# vis-spi-out.net
KiCad netlist of a schematic drawn in EAGLE
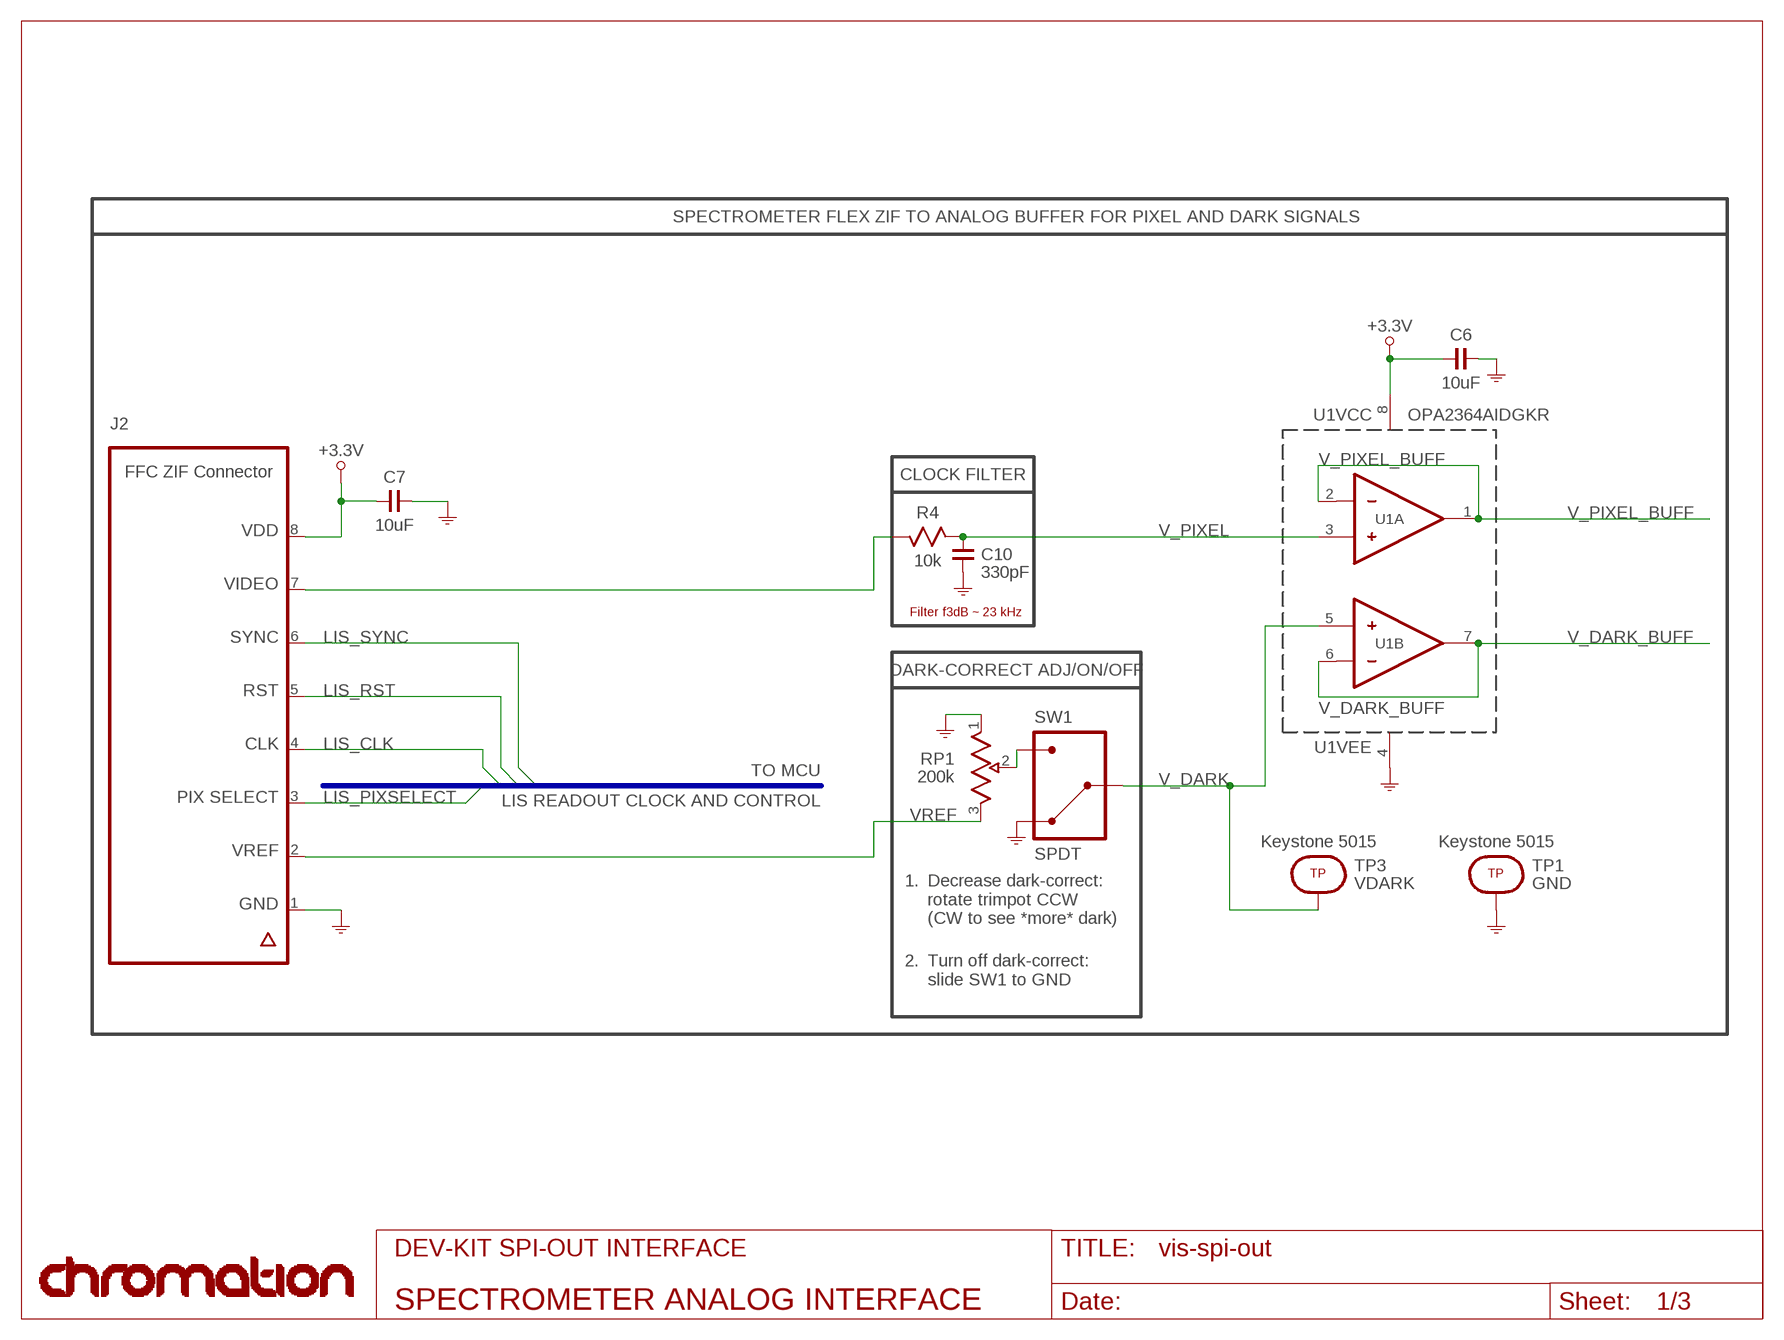
[diagram p0: schematic, sheet 1]
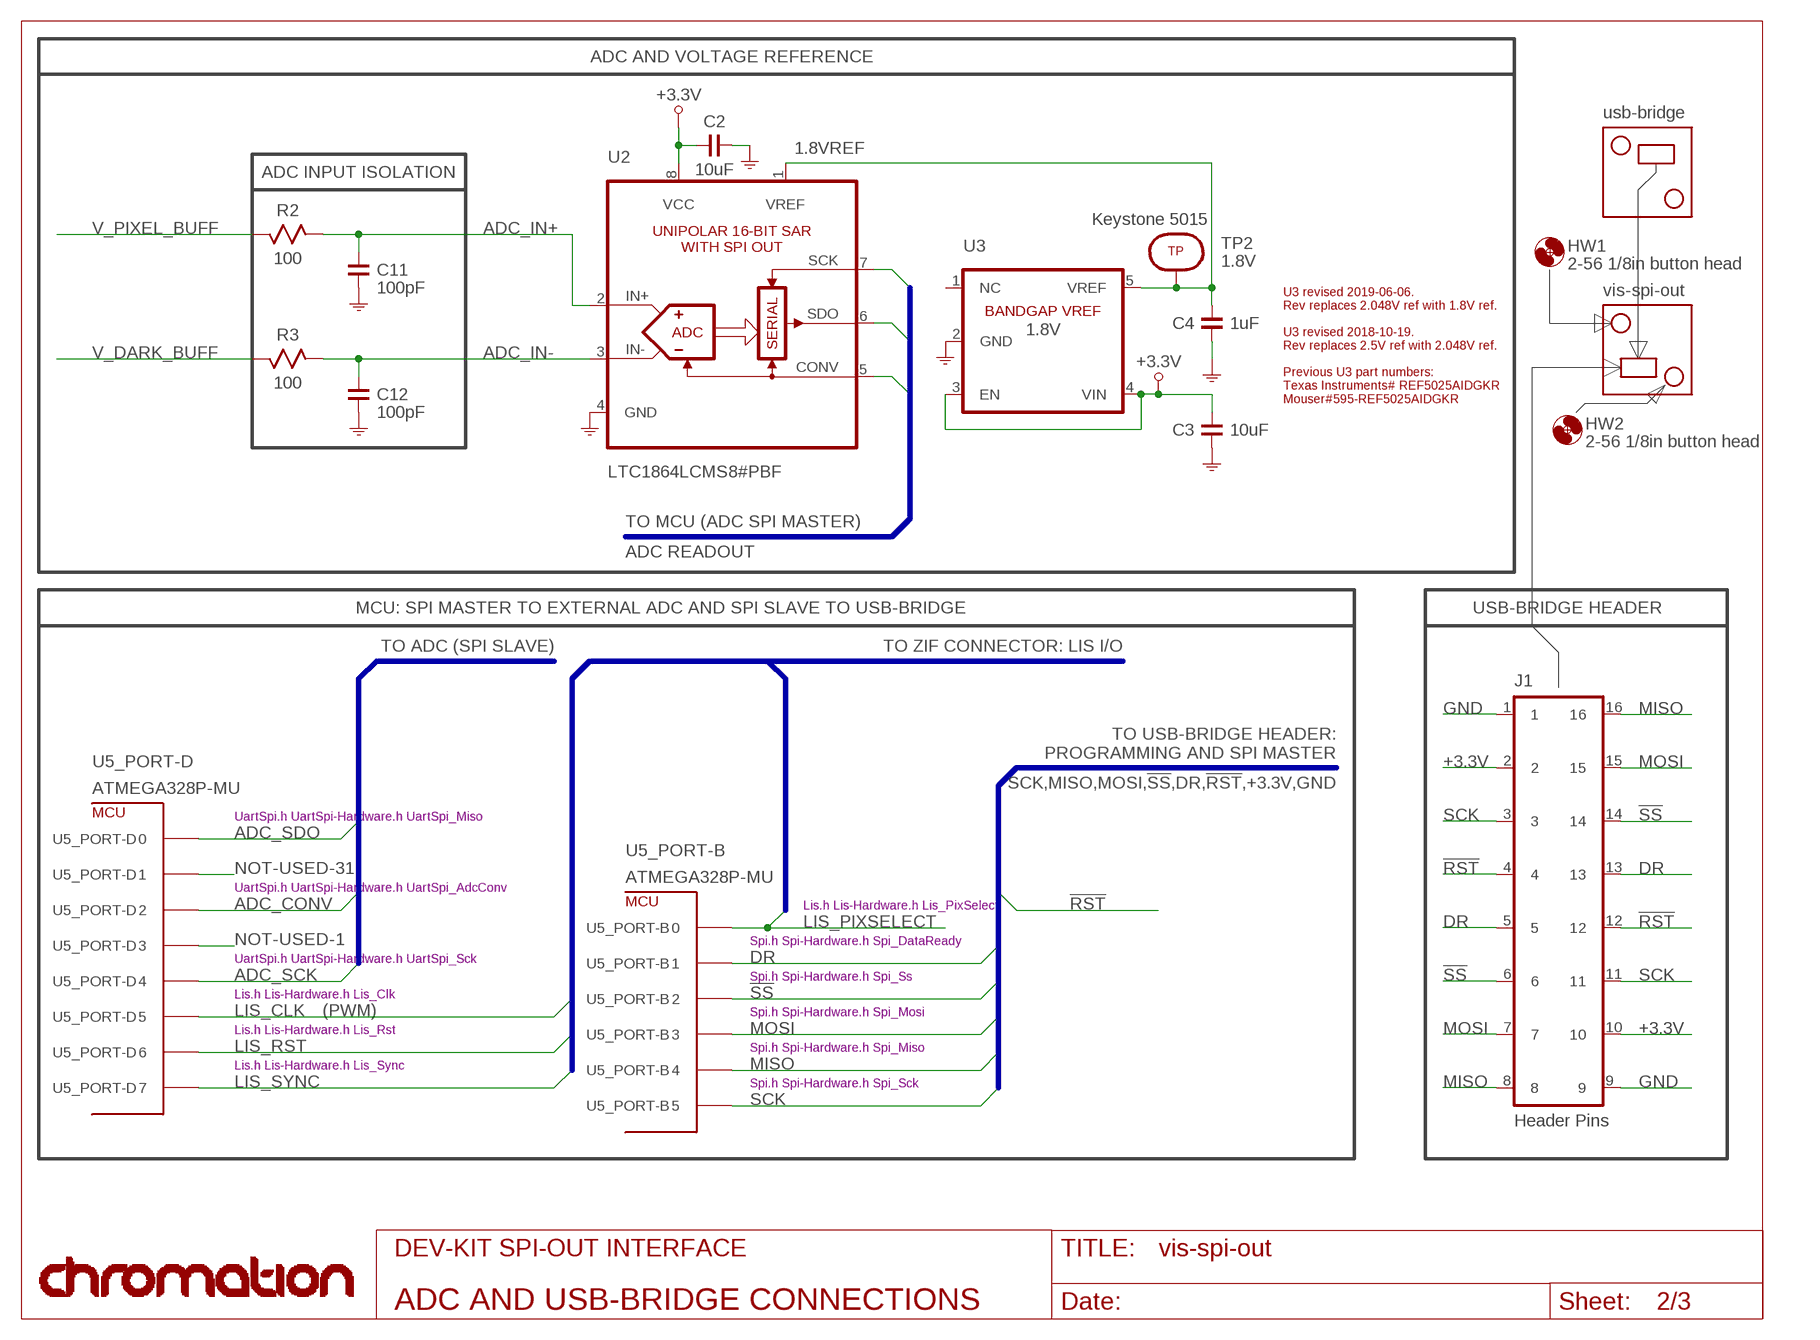
[diagram p1: schematic, sheet 2]
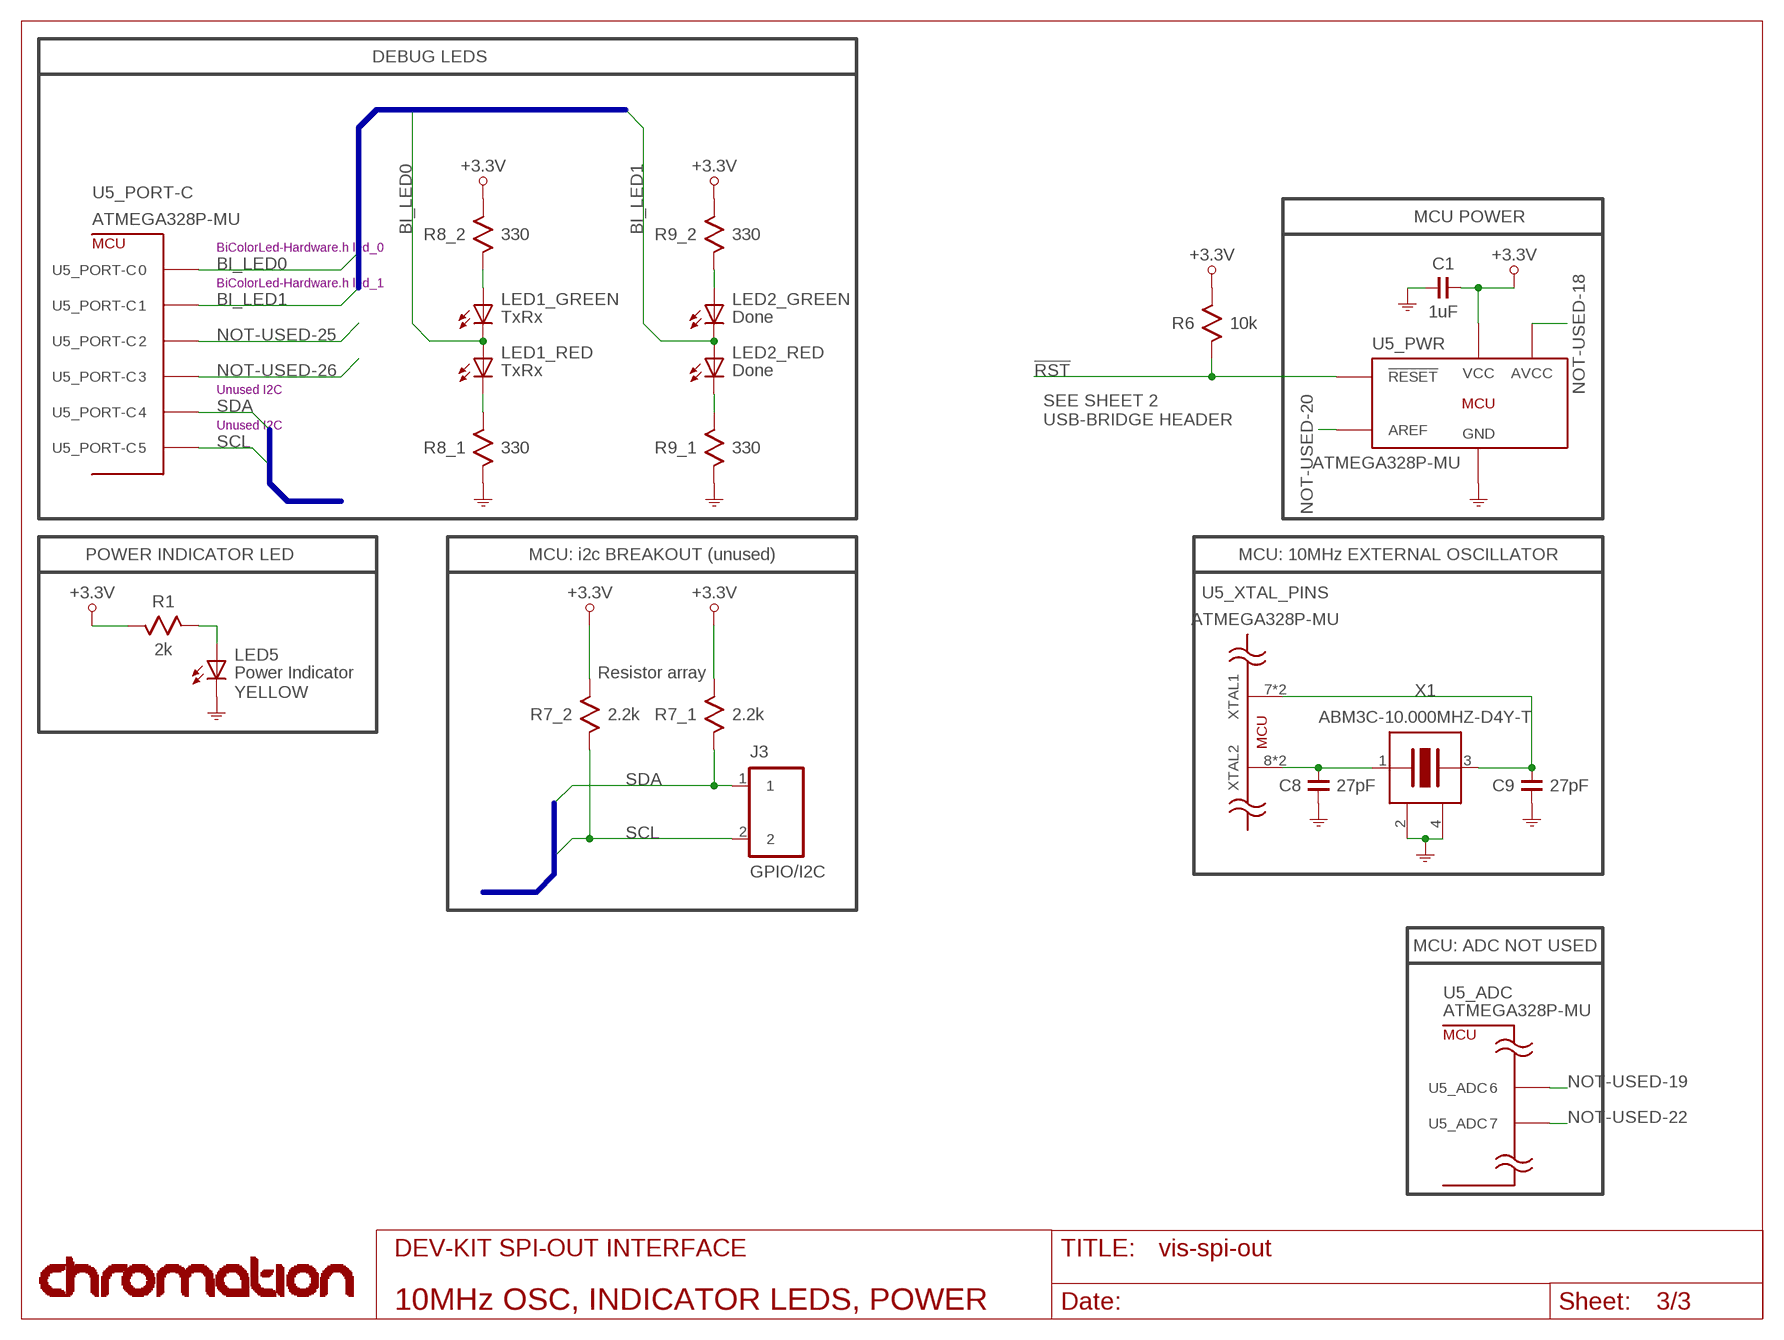
[diagram p2: schematic, sheet 3]

(export (version "E")
  (design (tool "Eeschema 10.0.6"))
  (components
    (comp (ref "C2")
      (value "10uF")
      (footprint "eagle-import:0603")
      (libsource (lib "eagle-import") (part "C_0603"))
    )
    (comp (ref "C3")
      (value "10uF")
      (footprint "eagle-import:0603")
      (libsource (lib "eagle-import") (part "C_0603"))
    )
    (comp (ref "C4")
      (value "1uF")
      (footprint "eagle-import:0603")
      (libsource (lib "eagle-import") (part "C_0603"))
    )
    (comp (ref "C11")
      (value "100pF")
      (footprint "eagle-import:0603")
      (libsource (lib "eagle-import") (part "C_0603"))
    )
    (comp (ref "C12")
      (value "100pF")
      (footprint "eagle-import:0603")
      (libsource (lib "eagle-import") (part "C_0603"))
    )
    (comp (ref "HW1")
      (value "2-56 1/8in button head")
      (footprint "eagle-import:MCMASTER_92949A081")
      (libsource (lib "eagle-import") (part "MOUNTING-HOLE_2-56_SCREW"))
    )
    (comp (ref "HW2")
      (value "2-56 1/8in button head")
      (footprint "eagle-import:MCMASTER_92949A081")
      (libsource (lib "eagle-import") (part "MOUNTING-HOLE_2-56_SCREW"))
    )
    (comp (ref "J1")
      (value "Header Pins")
      (footprint "eagle-import:TSM-108-01-S-DV")
      (libsource (lib "eagle-import") (part "HEADER-PIN_2X8"))
    )
    (comp (ref "R2")
      (value "100")
      (footprint "eagle-import:0603")
      (libsource (lib "eagle-import") (part "R_0603"))
    )
    (comp (ref "R3")
      (value "100")
      (footprint "eagle-import:0603")
      (libsource (lib "eagle-import") (part "R_0603"))
    )
    (comp (ref "ROTATED-USB-BRIDGE-PCB")
      (value "USB-BRIDGE_FOOTPRINT-AND-USB-REF")
      (footprint "eagle-import:OUTLINE-HEADER-MICROUSB")
      (libsource (lib "eagle-import") (part "USB-BRIDGE_FOOTPRINT-AND-USB-REF"))
    )
    (comp (ref "TP2")
      (value "Keystone 5015")
      (footprint "eagle-import:SMT-TEST-POINT-5015")
      (fields (field (name "TP_SIGNAL_NAME") "1.8V"))
      (libsource (lib "eagle-import") (part "TEST-POINT_SMT-5015"))
    )
    (comp (ref "U2")
      (value "LTC1864LCMS8#PBF")
      (footprint "eagle-import:LTC1864LCMS8")
      (libsource (lib "eagle-import") (part "LTC1864L_CMS8"))
    )
    (comp (ref "U3")
      (value "1.8V")
      (footprint "eagle-import:SOT23")
      (libsource (lib "eagle-import") (part "VREF_SOT23-LM4132"))
    )
    (comp (ref "U5")
      (value "ATMEGA328P-MU")
      (footprint "eagle-import:QFN-32_ATMEL")
      (fields
        (field (name "EXPORT") "YES")
        (field (name "MANUF") "Atmel")
        (field (name "MANUF_PNUM") "ATMEGA328P-MUR")
        (field (name "NOTES") "8-bit MCU: 10MHz at 3.3V, two SPI, and a PWM.")
        (field (name "VENDOR1") "Mouser")
        (field (name "VENDOR1_PNUM") "556-ATMEGA328P-MUR")
        (field (name "VENDOR1_PQ_00001") "3.57")
      )
      (libsource (lib "eagle-import") (part "ATMEGA328P-MU"))
    )
    (comp (ref "USB-BRDIGE-PCB")
      (value "USB-BRIDGE_FOOTPRINT-AND-USB-REF")
      (footprint "eagle-import:OUTLINE-HEADER-MICROUSB")
      (libsource (lib "eagle-import") (part "USB-BRIDGE_FOOTPRINT-AND-USB-REF"))
    )
    (comp (ref "C6")
      (value "10uF")
      (footprint "eagle-import:0603")
      (libsource (lib "eagle-import") (part "C_0603"))
    )
    (comp (ref "C7")
      (value "10uF")
      (footprint "eagle-import:0603")
      (libsource (lib "eagle-import") (part "C_0603"))
    )
    (comp (ref "C10")
      (value "330pF")
      (footprint "eagle-import:0603")
      (libsource (lib "eagle-import") (part "C_0603"))
    )
    (comp (ref "J2")
      (value "FFC ZIF Connector")
      (footprint "eagle-import:FH12-8S-0.5SH")
      (libsource (lib "eagle-import") (part "ZIF_8-PIN"))
    )
    (comp (ref "R4")
      (value "10k")
      (footprint "eagle-import:0603")
      (libsource (lib "eagle-import") (part "R_0603"))
    )
    (comp (ref "RP1")
      (value "200k")
      (footprint "eagle-import:TC3XX-2-204E")
      (libsource (lib "eagle-import") (part "TRIMPOT_3MM-SMD"))
    )
    (comp (ref "SW1")
      (value "SPDT")
      (footprint "eagle-import:JS102011JCQN")
      (libsource (lib "eagle-import") (part "SW_SPDT_JS102011JCQN"))
    )
    (comp (ref "TP1")
      (value "Keystone 5015")
      (footprint "eagle-import:SMT-TEST-POINT-5015")
      (fields (field (name "TP_SIGNAL_NAME") "GND"))
      (libsource (lib "eagle-import") (part "TEST-POINT_SMT-5015"))
    )
    (comp (ref "TP3")
      (value "Keystone 5015")
      (footprint "eagle-import:SMT-TEST-POINT-5015")
      (fields (field (name "TP_SIGNAL_NAME") "VDARK"))
      (libsource (lib "eagle-import") (part "TEST-POINT_SMT-5015"))
    )
    (comp (ref "U1")
      (value "OPA2364AIDGKR")
      (footprint "eagle-import:DGK")
      (fields
        (field (name "EXPORT") "YES")
        (field (name "MANUF") "Texas Instruments")
        (field (name "MANUF_PNUM") "OPA2364AIDGKR")
        (field (name "NOTES") "Dual op-amp to drive the SAR ADC S/H input. Settles to 0.01% (6.5LSB) in 1.5us.")
        (field (name "VENDOR1") "Mouser")
        (field (name "VENDOR1_PNUM") "595-OPA2364AIDGKR")
        (field (name "VENDOR1_PQ_00001") "2.64")
      )
      (libsource (lib "eagle-import") (part "OPA2364_VSSOP-8"))
    )
    (comp (ref "C1")
      (value "1uF")
      (footprint "eagle-import:0603")
      (libsource (lib "eagle-import") (part "C_0603"))
    )
    (comp (ref "C8")
      (value "27pF")
      (footprint "eagle-import:0603")
      (libsource (lib "eagle-import") (part "C_0603"))
    )
    (comp (ref "C9")
      (value "27pF")
      (footprint "eagle-import:0603")
      (libsource (lib "eagle-import") (part "C_0603"))
    )
    (comp (ref "J3")
      (value "GPIO/I2C")
      (footprint "eagle-import:SSM-102-S-SV")
      (libsource (lib "eagle-import") (part "HEADER-SOCKET-02_SSM-102-S-SV"))
    )
    (comp (ref "LED1")
      (value "TxRx")
      (footprint "eagle-import:HSMF-C16X")
      (fields
        (field (name "EXPORT") "YES")
        (field (name "MANUF") "Avago")
        (field (name "MANUF_PNUM") "HSMF-C165")
        (field (name "NOTES") "Bi-color LED")
        (field (name "VENDOR1") "Digi-Key")
        (field (name "VENDOR1_PNUM") "516-1419-1-ND")
        (field (name "VENDOR1_PQ_00001") "0.59")
      )
      (libsource (lib "eagle-import") (part "BICOLOR-LED_HSMF-C16X"))
    )
    (comp (ref "LED2")
      (value "Done")
      (footprint "eagle-import:HSMF-C16X")
      (fields
        (field (name "EXPORT") "YES")
        (field (name "MANUF") "Avago")
        (field (name "MANUF_PNUM") "HSMF-C165")
        (field (name "NOTES") "Bi-color LED")
        (field (name "VENDOR1") "Digi-Key")
        (field (name "VENDOR1_PNUM") "516-1419-1-ND")
        (field (name "VENDOR1_PQ_00001") "0.59")
      )
      (libsource (lib "eagle-import") (part "BICOLOR-LED_HSMF-C16X"))
    )
    (comp (ref "LED5")
      (value "Power Indicator")
      (footprint "eagle-import:LED-0603-KINGBRIGHT")
      (libsource (lib "eagle-import") (part "APTD1608SYCK_LED-0603"))
    )
    (comp (ref "R1")
      (value "2k")
      (footprint "eagle-import:0603")
      (libsource (lib "eagle-import") (part "R_0603"))
    )
    (comp (ref "R6")
      (value "10k")
      (footprint "eagle-import:0603")
      (libsource (lib "eagle-import") (part "R_0603"))
    )
    (comp (ref "R7")
      (value "2.2k")
      (footprint "eagle-import:742C043")
      (fields
        (field (name "EXPORT") "YES")
        (field (name "MANUF") "CTS Electronic Components")
        (field (name "MANUF_PNUM") "742C043222JP")
        (field (name "NOTES") "Array of 2 isolated resistors, 5% resistance tolerance, concave terminations.")
        (field (name "VENDOR1") "Mouser")
        (field (name "VENDOR1_PNUM") "774-742C043222JP")
        (field (name "VENDOR1_PQ_00001") "0.10")
      )
      (libsource (lib "eagle-import") (part "R-ARRAY-2_742C043"))
    )
    (comp (ref "R8")
      (value "330")
      (footprint "eagle-import:742C043")
      (fields
        (field (name "EXPORT") "YES")
        (field (name "MANUF") "CTS Electronic Components")
        (field (name "MANUF_PNUM") "742C043331JP")
        (field (name "NOTES") "Array of 2 isolated resistors, 5% resistance tolerance, concave terminations.")
        (field (name "VENDOR1") "Mouser")
        (field (name "VENDOR1_PNUM") "774-742C043331JP")
        (field (name "VENDOR1_PQ_00001") "0.21")
      )
      (libsource (lib "eagle-import") (part "R-ARRAY-2_742C043"))
    )
    (comp (ref "R9")
      (value "330")
      (footprint "eagle-import:742C043")
      (fields
        (field (name "EXPORT") "YES")
        (field (name "MANUF") "CTS Electronic Components")
        (field (name "MANUF_PNUM") "742C043331JP")
        (field (name "NOTES") "Array of 2 isolated resistors, 5% resistance tolerance, concave terminations.")
        (field (name "VENDOR1") "Mouser")
        (field (name "VENDOR1_PNUM") "774-742C043331JP")
        (field (name "VENDOR1_PQ_00001") "0.21")
      )
      (libsource (lib "eagle-import") (part "R-ARRAY-2_742C043"))
    )
    (comp (ref "X1")
      (value "ABM3C-10.000MHZ-D4Y-T")
      (footprint "eagle-import:CRYSTAL")
      (libsource (lib "eagle-import") (part "CRYSTAL_ABM3C-10.000MHZ-D4Y-T"))
    )
  )
  (nets
    (net (code "1") (name "+3.3V") (class "Default")
      (node (ref "C1") (pin "2") (pinfunction "2_2") (pintype "passive"))
      (node (ref "C2") (pin "2") (pinfunction "2_2") (pintype "passive"))
      (node (ref "C3") (pin "1") (pinfunction "1_1") (pintype "passive"))
      (node (ref "C6") (pin "2") (pinfunction "2_2") (pintype "passive"))
      (node (ref "C7") (pin "2") (pinfunction "2_2") (pintype "passive"))
      (node (ref "J1") (pin "10") (pinfunction "10_10") (pintype "bidirectional"))
      (node (ref "J1") (pin "2") (pinfunction "2_2") (pintype "bidirectional"))
      (node (ref "J2") (pin "8") (pinfunction "8_8") (pintype "bidirectional"))
      (node (ref "R1") (pin "1") (pinfunction "1_1") (pintype "passive"))
      (node (ref "R6") (pin "2") (pinfunction "2_2") (pintype "passive"))
      (node (ref "R7") (pin "1") (pinfunction "1_1") (pintype "passive"))
      (node (ref "R7") (pin "3") (pinfunction "1_3") (pintype "passive"))
      (node (ref "R8") (pin "3") (pinfunction "1_3") (pintype "passive"))
      (node (ref "R9") (pin "3") (pinfunction "1_3") (pintype "passive"))
      (node (ref "U1") (pin "8") (pinfunction "VCC_8") (pintype "bidirectional"))
      (node (ref "U2") (pin "8") (pinfunction "VCC_8") (pintype "bidirectional"))
      (node (ref "U3") (pin "3") (pinfunction "EN_3") (pintype "input"))
      (node (ref "U3") (pin "4") (pinfunction "VIN_4") (pintype "bidirectional"))
      (node (ref "U5") (pin "4") (pinfunction "VCC_4") (pintype "bidirectional"))
      (node (ref "U5") (pin "4F") (pinfunction "VCC_4F") (pintype "bidirectional"))
      (node (ref "U5") (pin "6") (pinfunction "VCC_6") (pintype "bidirectional"))
      (node (ref "U5") (pin "6F") (pinfunction "VCC_6F") (pintype "bidirectional"))
    )
    (net (code "5") (name "1.8VREF") (class "Default")
      (node (ref "C4") (pin "2") (pinfunction "2_2") (pintype "passive"))
      (node (ref "TP2") (pin "1") (pinfunction "1_1") (pintype "bidirectional"))
      (node (ref "U2") (pin "1") (pinfunction "VREF_1") (pintype "bidirectional"))
      (node (ref "U3") (pin "5") (pinfunction "VREF_5") (pintype "bidirectional"))
    )
    (net (code "6") (name "ADC_CONV") (class "Default")
      (node (ref "U2") (pin "5") (pinfunction "CONV_5") (pintype "bidirectional"))
      (node (ref "U5") (pin "32") (pinfunction "2_32") (pintype "bidirectional"))
      (node (ref "U5") (pin "32F") (pinfunction "2_32F") (pintype "bidirectional"))
    )
    (net (code "7") (name "ADC_IN+") (class "Default")
      (node (ref "C11") (pin "1") (pinfunction "1_1") (pintype "passive"))
      (node (ref "R2") (pin "2") (pinfunction "2_2") (pintype "passive"))
      (node (ref "U2") (pin "2") (pinfunction "IN+_2") (pintype "bidirectional"))
    )
    (net (code "8") (name "ADC_IN-") (class "Default")
      (node (ref "C12") (pin "1") (pinfunction "1_1") (pintype "passive"))
      (node (ref "R3") (pin "2") (pinfunction "2_2") (pintype "passive"))
      (node (ref "U2") (pin "3") (pinfunction "IN-_3") (pintype "bidirectional"))
    )
    (net (code "9") (name "ADC_SCK") (class "Default")
      (node (ref "U2") (pin "7") (pinfunction "SCK_7") (pintype "bidirectional"))
      (node (ref "U5") (pin "2") (pinfunction "4_2") (pintype "bidirectional"))
      (node (ref "U5") (pin "2F") (pinfunction "4_2F") (pintype "bidirectional"))
    )
    (net (code "10") (name "ADC_SDO") (class "Default")
      (node (ref "U2") (pin "6") (pinfunction "SDO_6") (pintype "bidirectional"))
      (node (ref "U5") (pin "30") (pinfunction "0_30") (pintype "bidirectional"))
      (node (ref "U5") (pin "30F") (pinfunction "0_30F") (pintype "bidirectional"))
    )
    (net (code "11") (name "BI_LED0") (class "Default")
      (node (ref "LED1") (pin "2") (pinfunction "A_2") (pintype "bidirectional"))
      (node (ref "LED1") (pin "3") (pinfunction "C_3") (pintype "bidirectional"))
      (node (ref "U5") (pin "23") (pinfunction "0_23") (pintype "bidirectional"))
      (node (ref "U5") (pin "23F") (pinfunction "0_23F") (pintype "bidirectional"))
    )
    (net (code "12") (name "BI_LED1") (class "Default")
      (node (ref "LED2") (pin "2") (pinfunction "A_2") (pintype "bidirectional"))
      (node (ref "LED2") (pin "3") (pinfunction "C_3") (pintype "bidirectional"))
      (node (ref "U5") (pin "24") (pinfunction "1_24") (pintype "bidirectional"))
      (node (ref "U5") (pin "24F") (pinfunction "1_24F") (pintype "bidirectional"))
    )
    (net (code "13") (name "DR") (class "Default")
      (node (ref "J1") (pin "13") (pinfunction "13_13") (pintype "bidirectional"))
      (node (ref "J1") (pin "5") (pinfunction "5_5") (pintype "bidirectional"))
      (node (ref "U5") (pin "13") (pinfunction "1_13") (pintype "bidirectional"))
      (node (ref "U5") (pin "13F") (pinfunction "1_13F") (pintype "bidirectional"))
    )
    (net (code "14") (name "GND") (class "Default")
      (node (ref "C1") (pin "1") (pinfunction "1_1") (pintype "passive"))
      (node (ref "C10") (pin "2") (pinfunction "2_2") (pintype "passive"))
      (node (ref "C11") (pin "2") (pinfunction "2_2") (pintype "passive"))
      (node (ref "C12") (pin "2") (pinfunction "2_2") (pintype "passive"))
      (node (ref "C2") (pin "1") (pinfunction "1_1") (pintype "passive"))
      (node (ref "C3") (pin "2") (pinfunction "2_2") (pintype "passive"))
      (node (ref "C4") (pin "1") (pinfunction "1_1") (pintype "passive"))
      (node (ref "C6") (pin "1") (pinfunction "1_1") (pintype "passive"))
      (node (ref "C7") (pin "1") (pinfunction "1_1") (pintype "passive"))
      (node (ref "C8") (pin "2") (pinfunction "2_2") (pintype "passive"))
      (node (ref "C9") (pin "2") (pinfunction "2_2") (pintype "passive"))
      (node (ref "J1") (pin "1") (pinfunction "1_1") (pintype "bidirectional"))
      (node (ref "J1") (pin "9") (pinfunction "9_9") (pintype "bidirectional"))
      (node (ref "J2") (pin "1") (pinfunction "1_1") (pintype "bidirectional"))
      (node (ref "LED5") (pin "2") (pinfunction "C_2") (pintype "bidirectional"))
      (node (ref "R8") (pin "2") (pinfunction "2_2") (pintype "passive"))
      (node (ref "R9") (pin "2") (pinfunction "2_2") (pintype "passive"))
      (node (ref "RP1") (pin "1") (pinfunction "CCW_1") (pintype "passive"))
      (node (ref "SW1") (pin "3") (pinfunction "3_3") (pintype "bidirectional"))
      (node (ref "TP1") (pin "1") (pinfunction "1_1") (pintype "bidirectional"))
      (node (ref "U1") (pin "4") (pinfunction "VEE_4") (pintype "bidirectional"))
      (node (ref "U2") (pin "4") (pinfunction "GND_4") (pintype "bidirectional"))
      (node (ref "U3") (pin "2") (pinfunction "GND_2") (pintype "bidirectional"))
      (node (ref "U5") (pin "21") (pinfunction "GND_21") (pintype "power_in"))
      (node (ref "U5") (pin "21F") (pinfunction "GND_21F") (pintype "power_in"))
      (node (ref "U5") (pin "3") (pinfunction "GND_3") (pintype "power_in"))
      (node (ref "U5") (pin "3F") (pinfunction "GND_3F") (pintype "power_in"))
      (node (ref "U5") (pin "5") (pinfunction "GND_5") (pintype "power_in"))
      (node (ref "U5") (pin "5F") (pinfunction "GND_5F") (pintype "power_in"))
      (node (ref "U5") (pin "THERMAL") (pinfunction "GND_THERMAL") (pintype "power_in"))
      (node (ref "X1") (pin "2") (pinfunction "GND_2") (pintype "power_in"))
      (node (ref "X1") (pin "4") (pinfunction "GND_4") (pintype "power_in"))
    )
    (net (code "15") (name "LIS_CLK") (class "Default")
      (node (ref "J2") (pin "4") (pinfunction "4_4") (pintype "bidirectional"))
      (node (ref "U5") (pin "9") (pinfunction "5_9") (pintype "bidirectional"))
      (node (ref "U5") (pin "9F") (pinfunction "5_9F") (pintype "bidirectional"))
    )
    (net (code "16") (name "LIS_PIXSELECT") (class "Default")
      (node (ref "J2") (pin "3") (pinfunction "3_3") (pintype "bidirectional"))
      (node (ref "U5") (pin "12") (pinfunction "0_12") (pintype "bidirectional"))
      (node (ref "U5") (pin "12F") (pinfunction "0_12F") (pintype "bidirectional"))
    )
    (net (code "17") (name "LIS_RST") (class "Default")
      (node (ref "J2") (pin "5") (pinfunction "5_5") (pintype "bidirectional"))
      (node (ref "U5") (pin "10") (pinfunction "6_10") (pintype "bidirectional"))
      (node (ref "U5") (pin "10F") (pinfunction "6_10F") (pintype "bidirectional"))
    )
    (net (code "18") (name "LIS_SYNC") (class "Default")
      (node (ref "J2") (pin "6") (pinfunction "6_6") (pintype "bidirectional"))
      (node (ref "U5") (pin "11") (pinfunction "7_11") (pintype "bidirectional"))
      (node (ref "U5") (pin "11F") (pinfunction "7_11F") (pintype "bidirectional"))
    )
    (net (code "19") (name "MISO") (class "Default")
      (node (ref "J1") (pin "16") (pinfunction "16_16") (pintype "bidirectional"))
      (node (ref "J1") (pin "8") (pinfunction "8_8") (pintype "bidirectional"))
      (node (ref "U5") (pin "16") (pinfunction "4_16") (pintype "bidirectional"))
      (node (ref "U5") (pin "16F") (pinfunction "4_16F") (pintype "bidirectional"))
    )
    (net (code "20") (name "MOSI") (class "Default")
      (node (ref "J1") (pin "15") (pinfunction "15_15") (pintype "bidirectional"))
      (node (ref "J1") (pin "7") (pinfunction "7_7") (pintype "bidirectional"))
      (node (ref "U5") (pin "15") (pinfunction "3_15") (pintype "bidirectional"))
      (node (ref "U5") (pin "15F") (pinfunction "3_15F") (pintype "bidirectional"))
    )
    (net (code "21") (name "NOT-USED-1") (class "Default")
      (node (ref "U5") (pin "1") (pinfunction "3_1") (pintype "bidirectional"))
      (node (ref "U5") (pin "1F") (pinfunction "3_1F") (pintype "bidirectional"))
    )
    (net (code "22") (name "NOT-USED-18") (class "Default")
      (node (ref "U5") (pin "18") (pinfunction "AVCC_18") (pintype "bidirectional"))
      (node (ref "U5") (pin "18F") (pinfunction "AVCC_18F") (pintype "bidirectional"))
    )
    (net (code "23") (name "NOT-USED-19") (class "Default")
      (node (ref "U5") (pin "19") (pinfunction "6_19") (pintype "bidirectional"))
      (node (ref "U5") (pin "19F") (pinfunction "6_19F") (pintype "bidirectional"))
    )
    (net (code "24") (name "NOT-USED-20") (class "Default")
      (node (ref "U5") (pin "20") (pinfunction "AREF_20") (pintype "bidirectional"))
      (node (ref "U5") (pin "20F") (pinfunction "AREF_20F") (pintype "bidirectional"))
    )
    (net (code "25") (name "NOT-USED-22") (class "Default")
      (node (ref "U5") (pin "22") (pinfunction "7_22") (pintype "bidirectional"))
      (node (ref "U5") (pin "22F") (pinfunction "7_22F") (pintype "bidirectional"))
    )
    (net (code "26") (name "NOT-USED-25") (class "Default")
      (node (ref "U5") (pin "25") (pinfunction "2_25") (pintype "bidirectional"))
      (node (ref "U5") (pin "25F") (pinfunction "2_25F") (pintype "bidirectional"))
    )
    (net (code "27") (name "NOT-USED-26") (class "Default")
      (node (ref "U5") (pin "26") (pinfunction "3_26") (pintype "bidirectional"))
      (node (ref "U5") (pin "26F") (pinfunction "3_26F") (pintype "bidirectional"))
    )
    (net (code "28") (name "NOT-USED-31") (class "Default")
      (node (ref "U5") (pin "31") (pinfunction "1_31") (pintype "bidirectional"))
      (node (ref "U5") (pin "31F") (pinfunction "1_31F") (pintype "bidirectional"))
    )
    (net (code "29") (name "Net-(C8-Pad1)") (class "Default")
      (node (ref "C8") (pin "1") (pinfunction "1_1") (pintype "passive"))
      (node (ref "U5") (pin "8") (pinfunction "XTAL2_8") (pintype "bidirectional"))
      (node (ref "U5") (pin "8F") (pinfunction "XTAL2_8F") (pintype "bidirectional"))
      (node (ref "X1") (pin "1") (pinfunction "1_1") (pintype "output"))
    )
    (net (code "30") (name "Net-(C9-Pad1)") (class "Default")
      (node (ref "C9") (pin "1") (pinfunction "1_1") (pintype "passive"))
      (node (ref "U5") (pin "7") (pinfunction "XTAL1_7") (pintype "bidirectional"))
      (node (ref "U5") (pin "7F") (pinfunction "XTAL1_7F") (pintype "bidirectional"))
      (node (ref "X1") (pin "3") (pinfunction "3_3") (pintype "output"))
    )
    (net (code "31") (name "Net-(J2-Pad7)") (class "Default")
      (node (ref "J2") (pin "7") (pinfunction "7_7") (pintype "bidirectional"))
      (node (ref "R4") (pin "1") (pinfunction "1_1") (pintype "passive"))
    )
    (net (code "32") (name "Net-(LED1A-A)") (class "Default")
      (node (ref "LED1") (pin "1") (pinfunction "A_1") (pintype "bidirectional"))
      (node (ref "R8") (pin "4") (pinfunction "2_4") (pintype "passive"))
    )
    (net (code "33") (name "Net-(LED1B-C)") (class "Default")
      (node (ref "LED1") (pin "4") (pinfunction "C_4") (pintype "bidirectional"))
      (node (ref "R8") (pin "1") (pinfunction "1_1") (pintype "passive"))
    )
    (net (code "34") (name "Net-(LED2A-A)") (class "Default")
      (node (ref "LED2") (pin "1") (pinfunction "A_1") (pintype "bidirectional"))
      (node (ref "R9") (pin "4") (pinfunction "2_4") (pintype "passive"))
    )
    (net (code "35") (name "Net-(LED2B-C)") (class "Default")
      (node (ref "LED2") (pin "4") (pinfunction "C_4") (pintype "bidirectional"))
      (node (ref "R9") (pin "1") (pinfunction "1_1") (pintype "passive"))
    )
    (net (code "36") (name "Net-(LED5-A)") (class "Default")
      (node (ref "LED5") (pin "1") (pinfunction "A_1") (pintype "bidirectional"))
      (node (ref "R1") (pin "2") (pinfunction "2_2") (pintype "passive"))
    )
    (net (code "37") (name "Net-(RP1-WIPER)") (class "Default")
      (node (ref "RP1") (pin "2") (pinfunction "WIPER_2") (pintype "passive"))
      (node (ref "SW1") (pin "1") (pinfunction "1_1") (pintype "bidirectional"))
    )
    (net (code "38") (name "SCK") (class "Default")
      (node (ref "J1") (pin "11") (pinfunction "11_11") (pintype "bidirectional"))
      (node (ref "J1") (pin "3") (pinfunction "3_3") (pintype "bidirectional"))
      (node (ref "U5") (pin "17") (pinfunction "5_17") (pintype "bidirectional"))
      (node (ref "U5") (pin "17F") (pinfunction "5_17F") (pintype "bidirectional"))
    )
    (net (code "39") (name "SCL") (class "Default")
      (node (ref "J3") (pin "2") (pinfunction "2_2") (pintype "bidirectional"))
      (node (ref "R7") (pin "4") (pinfunction "2_4") (pintype "passive"))
      (node (ref "U5") (pin "28") (pinfunction "5_28") (pintype "bidirectional"))
      (node (ref "U5") (pin "28F") (pinfunction "5_28F") (pintype "bidirectional"))
    )
    (net (code "40") (name "SDA") (class "Default")
      (node (ref "J3") (pin "1") (pinfunction "1_1") (pintype "bidirectional"))
      (node (ref "R7") (pin "2") (pinfunction "2_2") (pintype "passive"))
      (node (ref "U5") (pin "27") (pinfunction "4_27") (pintype "bidirectional"))
      (node (ref "U5") (pin "27F") (pinfunction "4_27F") (pintype "bidirectional"))
    )
    (net (code "41") (name "VREF") (class "Default")
      (node (ref "J2") (pin "2") (pinfunction "2_2") (pintype "bidirectional"))
      (node (ref "RP1") (pin "3") (pinfunction "CW_3") (pintype "passive"))
    )
    (net (code "42") (name "V_DARK") (class "Default")
      (node (ref "SW1") (pin "2") (pinfunction "2_2") (pintype "bidirectional"))
      (node (ref "TP3") (pin "1") (pinfunction "1_1") (pintype "bidirectional"))
      (node (ref "U1") (pin "5") (pinfunction "IN+_5") (pintype "bidirectional"))
    )
    (net (code "43") (name "V_DARK_BUFF") (class "Default")
      (node (ref "R3") (pin "1") (pinfunction "1_1") (pintype "passive"))
      (node (ref "U1") (pin "6") (pinfunction "IN-_6") (pintype "bidirectional"))
      (node (ref "U1") (pin "7") (pinfunction "OUT_7") (pintype "bidirectional"))
    )
    (net (code "44") (name "V_PIXEL") (class "Default")
      (node (ref "C10") (pin "1") (pinfunction "1_1") (pintype "passive"))
      (node (ref "R4") (pin "2") (pinfunction "2_2") (pintype "passive"))
      (node (ref "U1") (pin "3") (pinfunction "IN+_3") (pintype "bidirectional"))
    )
    (net (code "45") (name "V_PIXEL_BUFF") (class "Default")
      (node (ref "R2") (pin "1") (pinfunction "1_1") (pintype "passive"))
      (node (ref "U1") (pin "1") (pinfunction "OUT_1") (pintype "bidirectional"))
      (node (ref "U1") (pin "2") (pinfunction "IN-_2") (pintype "bidirectional"))
    )
    (net (code "46") (name "unconnected-(J2-LEG-PadLEG@1)") (class "Default")
      (node (ref "J2") (pin "LEG@1") (pinfunction "LEG_LEG@1") (pintype "no_connect"))
    )
    (net (code "47") (name "unconnected-(J2-LEG-PadLEG@2)") (class "Default")
      (node (ref "J2") (pin "LEG@2") (pinfunction "LEG_LEG@2") (pintype "no_connect"))
    )
    (net (code "48") (name "unconnected-(U3-NC-Pad1)") (class "Default")
      (node (ref "U3") (pin "1") (pinfunction "NC_1") (pintype "no_connect"))
    )
    (net (code "49") (name "~{RST}") (class "Default")
      (node (ref "J1") (pin "12") (pinfunction "12_12") (pintype "bidirectional"))
      (node (ref "J1") (pin "4") (pinfunction "4_4") (pintype "bidirectional"))
      (node (ref "R6") (pin "1") (pinfunction "1_1") (pintype "passive"))
      (node (ref "U5") (pin "29") (pinfunction "~{RESET}_29") (pintype "bidirectional"))
      (node (ref "U5") (pin "29F") (pinfunction "~{RESET}_29F") (pintype "bidirectional"))
    )
    (net (code "50") (name "~{SS}") (class "Default")
      (node (ref "J1") (pin "14") (pinfunction "14_14") (pintype "bidirectional"))
      (node (ref "J1") (pin "6") (pinfunction "6_6") (pintype "bidirectional"))
      (node (ref "U5") (pin "14") (pinfunction "2_14") (pintype "bidirectional"))
      (node (ref "U5") (pin "14F") (pinfunction "2_14F") (pintype "bidirectional"))
    )
  )
)
